# sensorAA.net
KiCad netlist of a schematic drawn in EAGLE
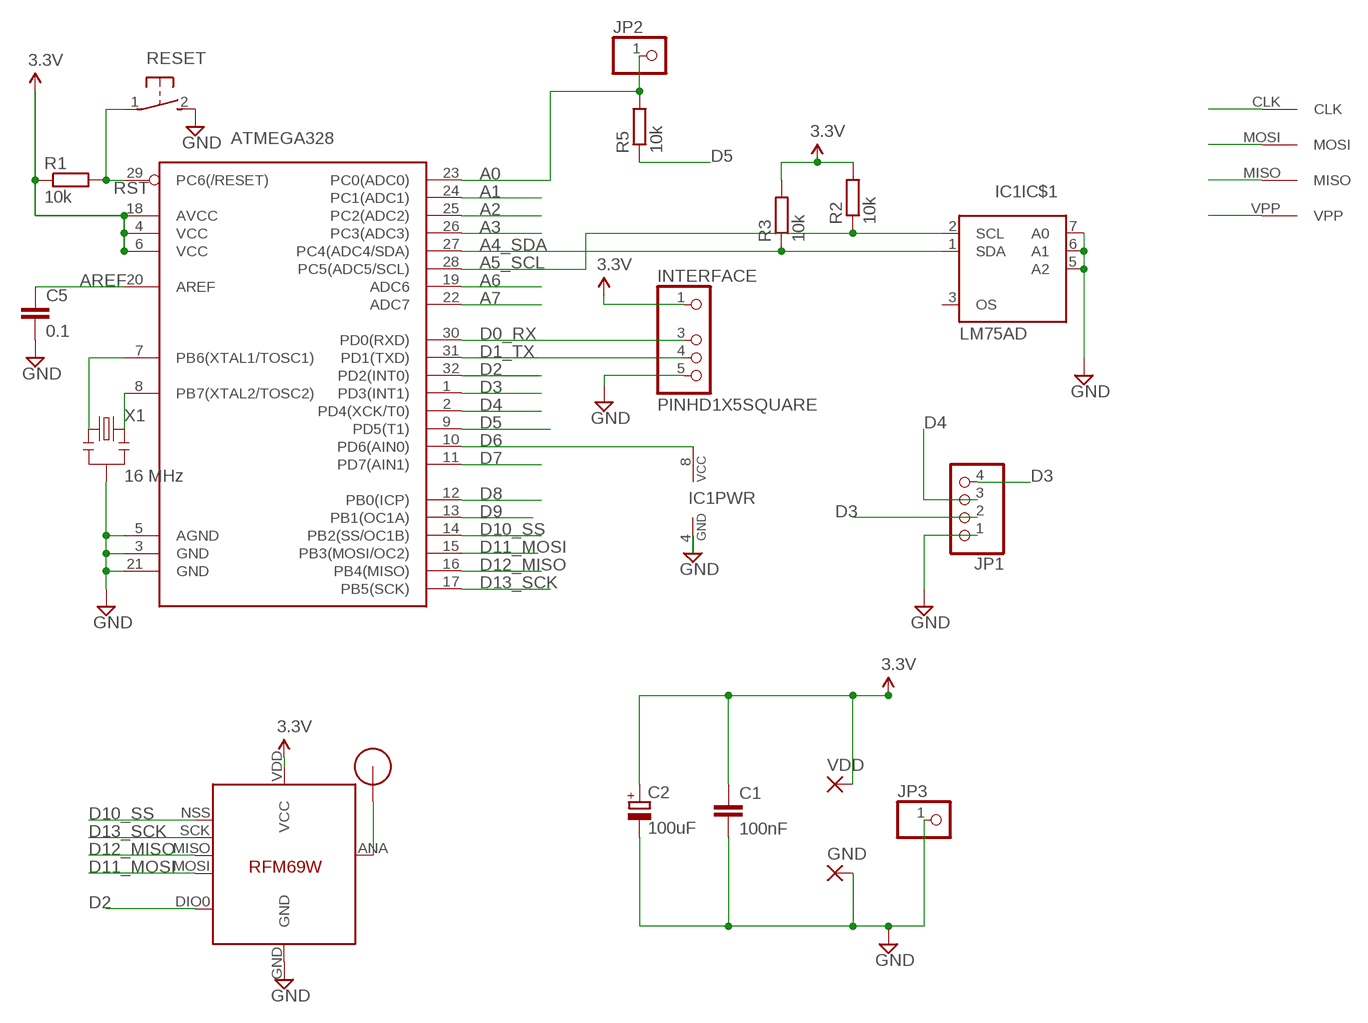
[diagram p0: schematic, sheet 1]

(export (version "E")
  (design (tool "Eeschema 10.0.6"))
  (components
    (comp (ref "ATMEGA328")
      (value "ATMega-328")
      (footprint "eagle-import:TQFP32-08")
      (libsource (lib "eagle-import") (part "ATMEGA168/328TQFP32"))
    )
    (comp (ref "C1")
      (value "100nF")
      (footprint "eagle-import:C2012")
      (libsource (lib "eagle-import") (part "C-EUC2012"))
    )
    (comp (ref "C2")
      (value "100uF")
      (footprint "eagle-import:SMC_B")
      (libsource (lib "eagle-import") (part "CPOL-EUSMCB"))
    )
    (comp (ref "C5")
      (value "0.1")
      (footprint "eagle-import:C2012")
      (libsource (lib "eagle-import") (part "C-EUC2012"))
    )
    (comp (ref "GND")
      (value "SMD5")
      (footprint "eagle-import:SMD2,54-5,08")
      (libsource (lib "eagle-import") (part "SMD5"))
    )
    (comp (ref "IC1")
      (value "LM75AD")
      (footprint "eagle-import:SO08")
      (libsource (lib "eagle-import") (part "LM75AD"))
    )
    (comp (ref "IC4")
      (value "RFM69")
      (footprint "eagle-import:RFM69W-MINPADS")
      (libsource (lib "eagle-import") (part "RFM69"))
    )
    (comp (ref "INTERFACE")
      (value "PINHD1X5SQUARE")
      (footprint "eagle-import:PINHD1X05-SQUARE")
      (libsource (lib "eagle-import") (part "PINHD1X5SQUARE"))
    )
    (comp (ref "JP1")
      (value "PINHD-1X04_2.54-S")
      (footprint "eagle-import:1X04-S")
      (libsource (lib "eagle-import") (part "PINHD-1X04_2.54-S"))
    )
    (comp (ref "JP2")
      (value "PINHD-1X01_2.54")
      (footprint "eagle-import:1X01")
      (libsource (lib "eagle-import") (part "PINHD-1X01_2.54"))
    )
    (comp (ref "JP3")
      (value "PINHD-1X01_2.54")
      (footprint "eagle-import:1X01")
      (libsource (lib "eagle-import") (part "PINHD-1X01_2.54"))
    )
    (comp (ref "R1")
      (value "10k")
      (footprint "eagle-import:R2012")
      (libsource (lib "eagle-import") (part "R-EU_R2012"))
    )
    (comp (ref "R2")
      (value "10k")
      (footprint "eagle-import:R2012")
      (libsource (lib "eagle-import") (part "R-EU_R2012"))
    )
    (comp (ref "R3")
      (value "10k")
      (footprint "eagle-import:R2012")
      (libsource (lib "eagle-import") (part "R-EU_R2012"))
    )
    (comp (ref "R5")
      (value "10k")
      (footprint "eagle-import:R2012")
      (libsource (lib "eagle-import") (part "R-EU_R2012"))
    )
    (comp (ref "RESET")
      (value "DTSM-3")
      (footprint "eagle-import:DTSM-3")
      (libsource (lib "eagle-import") (part "DTSM-3"))
    )
    (comp (ref "U$1")
      (value "RFM12B_ANTENNA")
      (footprint "eagle-import:RFM12B-ANTENNA")
      (libsource (lib "eagle-import") (part "RFM12B_ANTENNA"))
    )
    (comp (ref "U$2")
      (value "AVRHEADERDIP")
      (footprint "eagle-import:AVRHEADER")
      (libsource (lib "eagle-import") (part "AVRHEADERDIP"))
    )
    (comp (ref "VDD")
      (value "SMD5")
      (footprint "eagle-import:SMD2,54-5,08")
      (libsource (lib "eagle-import") (part "SMD5"))
    )
    (comp (ref "X1")
      (value "16 MHz")
      (footprint "eagle-import:RESONATOR-SMD")
      (libsource (lib "eagle-import") (part "RESONATORSMD"))
    )
  )
  (nets
    (net (code "1") (name "/A0") (class "Default")
      (node (ref "ATMEGA328") (pin "23") (pinfunction "PC0(ADC0)_23") (pintype "bidirectional"))
      (node (ref "JP2") (pin "1") (pinfunction "1_1") (pintype "passive"))
      (node (ref "R5") (pin "2") (pinfunction "2_2") (pintype "passive"))
    )
    (net (code "2") (name "/A1") (class "Default")
      (node (ref "ATMEGA328") (pin "24") (pinfunction "PC1(ADC1)_24") (pintype "bidirectional"))
    )
    (net (code "3") (name "/A2") (class "Default")
      (node (ref "ATMEGA328") (pin "25") (pinfunction "PC2(ADC2)_25") (pintype "bidirectional"))
    )
    (net (code "4") (name "/A3") (class "Default")
      (node (ref "ATMEGA328") (pin "26") (pinfunction "PC3(ADC3)_26") (pintype "bidirectional"))
    )
    (net (code "5") (name "/A4_SDA") (class "Default")
      (node (ref "ATMEGA328") (pin "27") (pinfunction "PC4(ADC4/SDA)_27") (pintype "bidirectional"))
      (node (ref "IC1") (pin "1") (pinfunction "SDA_1") (pintype "bidirectional"))
      (node (ref "R3") (pin "1") (pinfunction "1_1") (pintype "passive"))
    )
    (net (code "6") (name "/A5_SCL") (class "Default")
      (node (ref "ATMEGA328") (pin "28") (pinfunction "PC5(ADC5/SCL)_28") (pintype "bidirectional"))
      (node (ref "IC1") (pin "2") (pinfunction "SCL_2") (pintype "input"))
      (node (ref "R2") (pin "1") (pinfunction "1_1") (pintype "passive"))
    )
    (net (code "7") (name "/A6") (class "Default")
      (node (ref "ATMEGA328") (pin "19") (pinfunction "ADC6_19") (pintype "bidirectional"))
    )
    (net (code "8") (name "/A7") (class "Default")
      (node (ref "ATMEGA328") (pin "22") (pinfunction "ADC7_22") (pintype "bidirectional"))
    )
    (net (code "9") (name "/AREF") (class "Default")
      (node (ref "ATMEGA328") (pin "20") (pinfunction "AREF_20") (pintype "bidirectional"))
      (node (ref "C5") (pin "1") (pinfunction "1_1") (pintype "passive"))
    )
    (net (code "10") (name "/D0_RX") (class "Default")
      (node (ref "ATMEGA328") (pin "30") (pinfunction "PD0(RXD)_30") (pintype "bidirectional"))
      (node (ref "INTERFACE") (pin "3") (pinfunction "3_3") (pintype "passive"))
    )
    (net (code "11") (name "/D1_TX") (class "Default")
      (node (ref "ATMEGA328") (pin "31") (pinfunction "PD1(TXD)_31") (pintype "bidirectional"))
      (node (ref "INTERFACE") (pin "4") (pinfunction "4_4") (pintype "passive"))
    )
    (net (code "12") (name "/D2") (class "Default")
      (node (ref "ATMEGA328") (pin "32") (pinfunction "PD2(INT0)_32") (pintype "bidirectional"))
      (node (ref "IC4") (pin "DIO0") (pinfunction "DIO0_DIO0") (pintype "open_collector"))
    )
    (net (code "13") (name "/D3") (class "Default")
      (node (ref "ATMEGA328") (pin "1") (pinfunction "PD3(INT1)_1") (pintype "bidirectional"))
      (node (ref "JP1") (pin "2") (pinfunction "2_2") (pintype "passive"))
      (node (ref "JP1") (pin "4") (pinfunction "4_4") (pintype "passive"))
    )
    (net (code "14") (name "/D4") (class "Default")
      (node (ref "ATMEGA328") (pin "2") (pinfunction "PD4(XCK/T0)_2") (pintype "bidirectional"))
      (node (ref "JP1") (pin "3") (pinfunction "3_3") (pintype "passive"))
    )
    (net (code "15") (name "/D5") (class "Default")
      (node (ref "ATMEGA328") (pin "9") (pinfunction "PD5(T1)_9") (pintype "bidirectional"))
      (node (ref "R5") (pin "1") (pinfunction "1_1") (pintype "passive"))
    )
    (net (code "16") (name "/D6") (class "Default")
      (node (ref "ATMEGA328") (pin "10") (pinfunction "PD6(AIN0)_10") (pintype "bidirectional"))
      (node (ref "IC1") (pin "8") (pinfunction "VCC_8") (pintype "power_in"))
    )
    (net (code "17") (name "/D7") (class "Default")
      (node (ref "ATMEGA328") (pin "11") (pinfunction "PD7(AIN1)_11") (pintype "bidirectional"))
    )
    (net (code "18") (name "/D8") (class "Default")
      (node (ref "ATMEGA328") (pin "12") (pinfunction "PB0(ICP)_12") (pintype "bidirectional"))
    )
    (net (code "19") (name "/D9") (class "Default")
      (node (ref "ATMEGA328") (pin "13") (pinfunction "PB1(OC1A)_13") (pintype "bidirectional"))
    )
    (net (code "20") (name "/D10_SS") (class "Default")
      (node (ref "ATMEGA328") (pin "14") (pinfunction "PB2(SS/OC1B)_14") (pintype "bidirectional"))
      (node (ref "IC4") (pin "NSS") (pinfunction "SEL_NSS") (pintype "input"))
    )
    (net (code "21") (name "/D11_MOSI") (class "Default")
      (node (ref "ATMEGA328") (pin "15") (pinfunction "PB3(MOSI/OC2)_15") (pintype "bidirectional"))
      (node (ref "IC4") (pin "MOSI") (pinfunction "MOSI_MOSI") (pintype "output"))
      (node (ref "U$2") (pin "MOSI") (pinfunction "MOSI_MOSI") (pintype "bidirectional"))
    )
    (net (code "22") (name "/D12_MISO") (class "Default")
      (node (ref "ATMEGA328") (pin "16") (pinfunction "PB4(MISO)_16") (pintype "bidirectional"))
      (node (ref "IC4") (pin "MISO") (pinfunction "MISO_MISO") (pintype "input"))
      (node (ref "U$2") (pin "MISO") (pinfunction "MISO_MISO") (pintype "bidirectional"))
    )
    (net (code "23") (name "/D13_SCK") (class "Default")
      (node (ref "ATMEGA328") (pin "17") (pinfunction "PB5(SCK)_17") (pintype "bidirectional"))
      (node (ref "IC4") (pin "SCK") (pinfunction "SCK_SCK") (pintype "input"))
      (node (ref "U$2") (pin "CLK") (pinfunction "CLK_CLK") (pintype "bidirectional"))
    )
    (net (code "24") (name "/RST") (class "Default")
      (node (ref "ATMEGA328") (pin "29") (pinfunction "PC6(/RESET)_29") (pintype "bidirectional"))
      (node (ref "R1") (pin "2") (pinfunction "2_2") (pintype "passive"))
      (node (ref "RESET") (pin "1") (pinfunction "1_1") (pintype "passive"))
      (node (ref "U$2") (pin "VPP") (pinfunction "VPP_VPP") (pintype "bidirectional"))
    )
    (net (code "25") (name "3.3V") (class "Default")
      (node (ref "ATMEGA328") (pin "18") (pinfunction "AVCC_18") (pintype "bidirectional"))
      (node (ref "ATMEGA328") (pin "4") (pinfunction "VCC_4") (pintype "bidirectional"))
      (node (ref "ATMEGA328") (pin "6") (pinfunction "VCC_6") (pintype "bidirectional"))
      (node (ref "C1") (pin "1") (pinfunction "1_1") (pintype "passive"))
      (node (ref "C2") (pin "+") (pinfunction "+_+") (pintype "passive"))
      (node (ref "IC4") (pin "VDD") (pinfunction "VCC_VDD") (pintype "power_in"))
      (node (ref "INTERFACE") (pin "1") (pinfunction "1_1") (pintype "passive"))
      (node (ref "R1") (pin "1") (pinfunction "1_1") (pintype "passive"))
      (node (ref "R2") (pin "2") (pinfunction "2_2") (pintype "passive"))
      (node (ref "R3") (pin "2") (pinfunction "2_2") (pintype "passive"))
      (node (ref "VDD") (pin "1") (pinfunction "P_1") (pintype "passive"))
    )
    (net (code "26") (name "GND") (class "Default")
      (node (ref "ATMEGA328") (pin "21") (pinfunction "GND_21") (pintype "bidirectional"))
      (node (ref "ATMEGA328") (pin "3") (pinfunction "GND_3") (pintype "bidirectional"))
      (node (ref "ATMEGA328") (pin "5") (pinfunction "AGND_5") (pintype "bidirectional"))
      (node (ref "C1") (pin "2") (pinfunction "2_2") (pintype "passive"))
      (node (ref "C2") (pin "-") (pinfunction "-_-") (pintype "passive"))
      (node (ref "C5") (pin "2") (pinfunction "2_2") (pintype "passive"))
      (node (ref "GND") (pin "1") (pinfunction "P_1") (pintype "passive"))
      (node (ref "IC1") (pin "4") (pinfunction "GND_4") (pintype "power_in"))
      (node (ref "IC1") (pin "5") (pinfunction "A2_5") (pintype "input"))
      (node (ref "IC1") (pin "6") (pinfunction "A1_6") (pintype "input"))
      (node (ref "IC1") (pin "7") (pinfunction "A0_7") (pintype "input"))
      (node (ref "IC4") (pin "GND") (pinfunction "GND_GND") (pintype "power_in"))
      (node (ref "INTERFACE") (pin "5") (pinfunction "5_5") (pintype "passive"))
      (node (ref "JP1") (pin "1") (pinfunction "1_1") (pintype "passive"))
      (node (ref "JP3") (pin "1") (pinfunction "1_1") (pintype "passive"))
      (node (ref "RESET") (pin "2") (pinfunction "2_2") (pintype "passive"))
      (node (ref "X1") (pin "2") (pinfunction "2_2") (pintype "passive"))
    )
    (net (code "27") (name "Net-(ATMEGA328-PB6(XTAL1{slash}TOSC1))") (class "Default")
      (node (ref "ATMEGA328") (pin "7") (pinfunction "PB6(XTAL1/TOSC1)_7") (pintype "bidirectional"))
      (node (ref "X1") (pin "1") (pinfunction "1_1") (pintype "passive"))
    )
    (net (code "28") (name "Net-(ATMEGA328-PB7(XTAL2{slash}TOSC2))") (class "Default")
      (node (ref "ATMEGA328") (pin "8") (pinfunction "PB7(XTAL2/TOSC2)_8") (pintype "bidirectional"))
      (node (ref "X1") (pin "3") (pinfunction "3_3") (pintype "passive"))
    )
    (net (code "29") (name "Net-(IC4-ANT)") (class "Default")
      (node (ref "IC4") (pin "ANA") (pinfunction "ANT_ANA") (pintype "passive"))
      (node (ref "U$1") (pin "P$1") (pinfunction "1_P$1") (pintype "bidirectional"))
    )
    (net (code "30") (name "unconnected-(IC1A-OS-Pad3)") (class "Default")
      (node (ref "IC1") (pin "3") (pinfunction "OS_3") (pintype "output"))
    )
  )
)
